# mspfacedraft.net
KiCad netlist of a schematic drawn in EAGLE
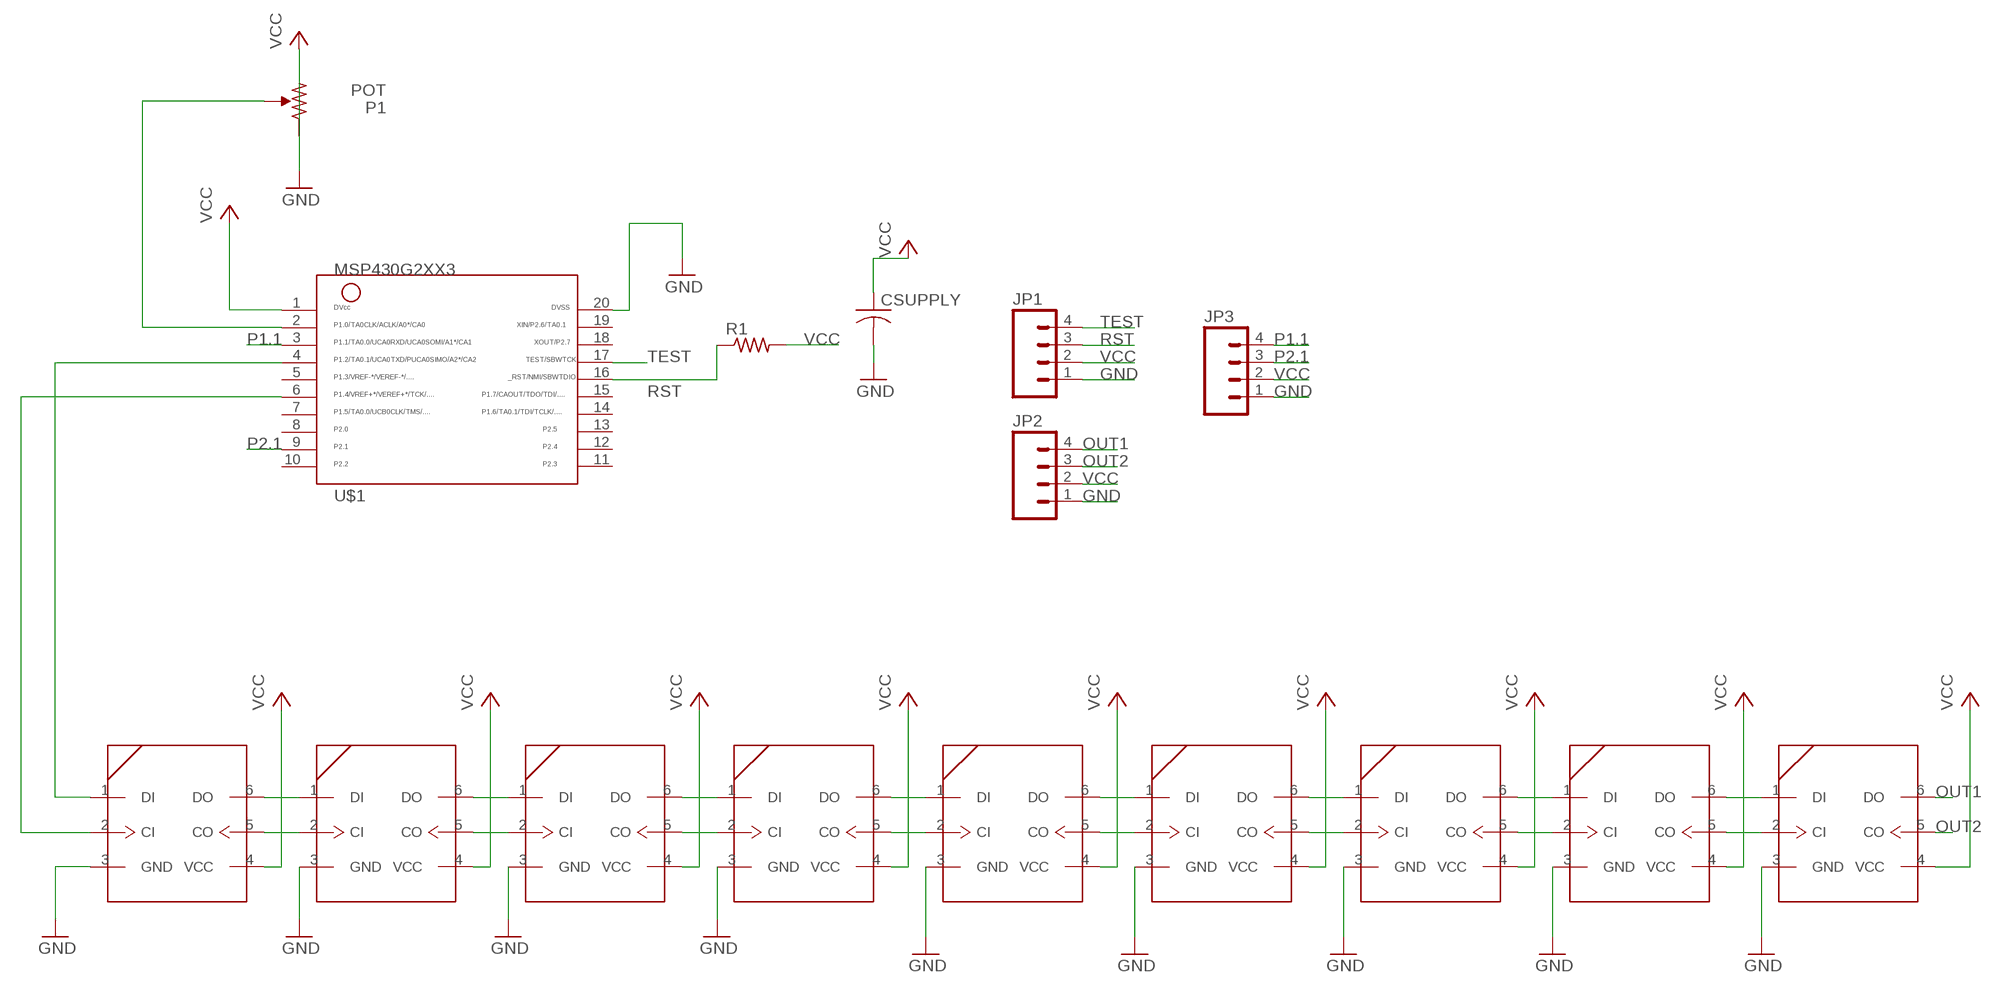
[diagram p0: schematic, sheet 1]

(export (version "E")
  (design (tool "Eeschema 10.0.6"))
  (components
    (comp (ref "CSUPPLY")
      (value "C-USC1206")
      (footprint "eagle-import:C1206")
      (libsource (lib "eagle-import") (part "C-USC1206"))
    )
    (comp (ref "JP1")
      (value "M04LOCK")
      (footprint "eagle-import:1X04_LOCK")
      (libsource (lib "eagle-import") (part "M04LOCK"))
    )
    (comp (ref "JP2")
      (value "M04LOCK")
      (footprint "eagle-import:1X04_LOCK")
      (libsource (lib "eagle-import") (part "M04LOCK"))
    )
    (comp (ref "JP3")
      (value "M04LOCK")
      (footprint "eagle-import:1X04_LOCK")
      (libsource (lib "eagle-import") (part "M04LOCK"))
    )
    (comp (ref "LED1")
      (value "APA102")
      (footprint "eagle-import:5050")
      (libsource (lib "eagle-import") (part "APA102"))
    )
    (comp (ref "LED2")
      (value "APA102")
      (footprint "eagle-import:5050")
      (libsource (lib "eagle-import") (part "APA102"))
    )
    (comp (ref "LED3")
      (value "APA102")
      (footprint "eagle-import:5050")
      (libsource (lib "eagle-import") (part "APA102"))
    )
    (comp (ref "LED4")
      (value "APA102")
      (footprint "eagle-import:5050")
      (libsource (lib "eagle-import") (part "APA102"))
    )
    (comp (ref "LED5")
      (value "APA102")
      (footprint "eagle-import:5050")
      (libsource (lib "eagle-import") (part "APA102"))
    )
    (comp (ref "LED6")
      (value "APA102")
      (footprint "eagle-import:5050")
      (libsource (lib "eagle-import") (part "APA102"))
    )
    (comp (ref "LED7")
      (value "APA102")
      (footprint "eagle-import:5050")
      (libsource (lib "eagle-import") (part "APA102"))
    )
    (comp (ref "LED8")
      (value "APA102")
      (footprint "eagle-import:5050")
      (libsource (lib "eagle-import") (part "APA102"))
    )
    (comp (ref "LED9")
      (value "APA102")
      (footprint "eagle-import:5050")
      (libsource (lib "eagle-import") (part "APA102"))
    )
    (comp (ref "P1")
      (value "POT")
      (footprint "eagle-import:POT")
      (libsource (lib "eagle-import") (part "POT"))
    )
    (comp (ref "R1")
      (value "R-US_R1206")
      (footprint "eagle-import:R1206")
      (libsource (lib "eagle-import") (part "R-US_R1206"))
    )
    (comp (ref "U$1")
      (value "MSP430G2XX3TSSOP")
      (footprint "eagle-import:PW20")
      (libsource (lib "eagle-import") (part "MSP430G2XX3TSSOP"))
    )
  )
  (nets
    (net (code "1") (name "/OUT1") (class "Default")
      (node (ref "JP2") (pin "4") (pinfunction "4_4") (pintype "passive"))
      (node (ref "LED9") (pin "6") (pinfunction "DO_6") (pintype "output"))
    )
    (net (code "2") (name "/OUT2") (class "Default")
      (node (ref "JP2") (pin "3") (pinfunction "3_3") (pintype "passive"))
      (node (ref "LED9") (pin "5") (pinfunction "CO_5") (pintype "output"))
    )
    (net (code "3") (name "/P1.1") (class "Default")
      (node (ref "JP3") (pin "4") (pinfunction "4_4") (pintype "passive"))
      (node (ref "U$1") (pin "3") (pinfunction "3_3") (pintype "bidirectional"))
    )
    (net (code "4") (name "/P2.1") (class "Default")
      (node (ref "JP3") (pin "3") (pinfunction "3_3") (pintype "passive"))
      (node (ref "U$1") (pin "9") (pinfunction "9_9") (pintype "bidirectional"))
    )
    (net (code "5") (name "/RST") (class "Default")
      (node (ref "JP1") (pin "3") (pinfunction "3_3") (pintype "passive"))
      (node (ref "R1") (pin "1") (pinfunction "1_1") (pintype "passive"))
      (node (ref "U$1") (pin "16") (pinfunction "16_16") (pintype "bidirectional"))
    )
    (net (code "6") (name "/TEST") (class "Default")
      (node (ref "JP1") (pin "4") (pinfunction "4_4") (pintype "passive"))
      (node (ref "U$1") (pin "17") (pinfunction "17_17") (pintype "bidirectional"))
    )
    (net (code "7") (name "GND") (class "Default")
      (node (ref "CSUPPLY") (pin "2") (pinfunction "2_2") (pintype "passive"))
      (node (ref "JP1") (pin "1") (pinfunction "1_1") (pintype "passive"))
      (node (ref "JP2") (pin "1") (pinfunction "1_1") (pintype "passive"))
      (node (ref "JP3") (pin "1") (pinfunction "1_1") (pintype "passive"))
      (node (ref "LED1") (pin "3") (pinfunction "GND_3") (pintype "power_in"))
      (node (ref "LED2") (pin "3") (pinfunction "GND_3") (pintype "power_in"))
      (node (ref "LED3") (pin "3") (pinfunction "GND_3") (pintype "power_in"))
      (node (ref "LED4") (pin "3") (pinfunction "GND_3") (pintype "power_in"))
      (node (ref "LED5") (pin "3") (pinfunction "GND_3") (pintype "power_in"))
      (node (ref "LED6") (pin "3") (pinfunction "GND_3") (pintype "power_in"))
      (node (ref "LED7") (pin "3") (pinfunction "GND_3") (pintype "power_in"))
      (node (ref "LED8") (pin "3") (pinfunction "GND_3") (pintype "power_in"))
      (node (ref "LED9") (pin "3") (pinfunction "GND_3") (pintype "power_in"))
      (node (ref "P1") (pin "GND") (pinfunction "CW_GND") (pintype "passive"))
      (node (ref "U$1") (pin "20") (pinfunction "20_20") (pintype "bidirectional"))
    )
    (net (code "8") (name "Net-(LED1-CI)") (class "Default")
      (node (ref "LED1") (pin "2") (pinfunction "CI_2") (pintype "input"))
      (node (ref "U$1") (pin "6") (pinfunction "6_6") (pintype "bidirectional"))
    )
    (net (code "9") (name "Net-(LED1-CO)") (class "Default")
      (node (ref "LED1") (pin "5") (pinfunction "CO_5") (pintype "output"))
      (node (ref "LED2") (pin "2") (pinfunction "CI_2") (pintype "input"))
    )
    (net (code "10") (name "Net-(LED1-DI)") (class "Default")
      (node (ref "LED1") (pin "1") (pinfunction "DI_1") (pintype "input"))
      (node (ref "U$1") (pin "4") (pinfunction "4_4") (pintype "bidirectional"))
    )
    (net (code "11") (name "Net-(LED1-DO)") (class "Default")
      (node (ref "LED1") (pin "6") (pinfunction "DO_6") (pintype "output"))
      (node (ref "LED2") (pin "1") (pinfunction "DI_1") (pintype "input"))
    )
    (net (code "12") (name "Net-(LED2-CO)") (class "Default")
      (node (ref "LED2") (pin "5") (pinfunction "CO_5") (pintype "output"))
      (node (ref "LED3") (pin "2") (pinfunction "CI_2") (pintype "input"))
    )
    (net (code "13") (name "Net-(LED2-DO)") (class "Default")
      (node (ref "LED2") (pin "6") (pinfunction "DO_6") (pintype "output"))
      (node (ref "LED3") (pin "1") (pinfunction "DI_1") (pintype "input"))
    )
    (net (code "14") (name "Net-(LED3-CO)") (class "Default")
      (node (ref "LED3") (pin "5") (pinfunction "CO_5") (pintype "output"))
      (node (ref "LED4") (pin "2") (pinfunction "CI_2") (pintype "input"))
    )
    (net (code "15") (name "Net-(LED3-DO)") (class "Default")
      (node (ref "LED3") (pin "6") (pinfunction "DO_6") (pintype "output"))
      (node (ref "LED4") (pin "1") (pinfunction "DI_1") (pintype "input"))
    )
    (net (code "16") (name "Net-(LED4-CO)") (class "Default")
      (node (ref "LED4") (pin "5") (pinfunction "CO_5") (pintype "output"))
      (node (ref "LED5") (pin "2") (pinfunction "CI_2") (pintype "input"))
    )
    (net (code "17") (name "Net-(LED4-DO)") (class "Default")
      (node (ref "LED4") (pin "6") (pinfunction "DO_6") (pintype "output"))
      (node (ref "LED5") (pin "1") (pinfunction "DI_1") (pintype "input"))
    )
    (net (code "18") (name "Net-(LED5-CO)") (class "Default")
      (node (ref "LED5") (pin "5") (pinfunction "CO_5") (pintype "output"))
      (node (ref "LED6") (pin "2") (pinfunction "CI_2") (pintype "input"))
    )
    (net (code "19") (name "Net-(LED5-DO)") (class "Default")
      (node (ref "LED5") (pin "6") (pinfunction "DO_6") (pintype "output"))
      (node (ref "LED6") (pin "1") (pinfunction "DI_1") (pintype "input"))
    )
    (net (code "20") (name "Net-(LED6-CO)") (class "Default")
      (node (ref "LED6") (pin "5") (pinfunction "CO_5") (pintype "output"))
      (node (ref "LED7") (pin "2") (pinfunction "CI_2") (pintype "input"))
    )
    (net (code "21") (name "Net-(LED6-DO)") (class "Default")
      (node (ref "LED6") (pin "6") (pinfunction "DO_6") (pintype "output"))
      (node (ref "LED7") (pin "1") (pinfunction "DI_1") (pintype "input"))
    )
    (net (code "22") (name "Net-(LED7-CO)") (class "Default")
      (node (ref "LED7") (pin "5") (pinfunction "CO_5") (pintype "output"))
      (node (ref "LED8") (pin "2") (pinfunction "CI_2") (pintype "input"))
    )
    (net (code "23") (name "Net-(LED7-DO)") (class "Default")
      (node (ref "LED7") (pin "6") (pinfunction "DO_6") (pintype "output"))
      (node (ref "LED8") (pin "1") (pinfunction "DI_1") (pintype "input"))
    )
    (net (code "24") (name "Net-(LED8-CO)") (class "Default")
      (node (ref "LED8") (pin "5") (pinfunction "CO_5") (pintype "output"))
      (node (ref "LED9") (pin "2") (pinfunction "CI_2") (pintype "input"))
    )
    (net (code "25") (name "Net-(LED8-DO)") (class "Default")
      (node (ref "LED8") (pin "6") (pinfunction "DO_6") (pintype "output"))
      (node (ref "LED9") (pin "1") (pinfunction "DI_1") (pintype "input"))
    )
    (net (code "26") (name "Net-(P1-S)") (class "Default")
      (node (ref "P1") (pin "SIG") (pinfunction "S_SIG") (pintype "bidirectional"))
      (node (ref "U$1") (pin "2") (pinfunction "2_2") (pintype "bidirectional"))
    )
    (net (code "27") (name "VCC") (class "Default")
      (node (ref "CSUPPLY") (pin "1") (pinfunction "1_1") (pintype "passive"))
      (node (ref "JP1") (pin "2") (pinfunction "2_2") (pintype "passive"))
      (node (ref "JP2") (pin "2") (pinfunction "2_2") (pintype "passive"))
      (node (ref "JP3") (pin "2") (pinfunction "2_2") (pintype "passive"))
      (node (ref "LED1") (pin "4") (pinfunction "VCC_4") (pintype "power_in"))
      (node (ref "LED2") (pin "4") (pinfunction "VCC_4") (pintype "power_in"))
      (node (ref "LED3") (pin "4") (pinfunction "VCC_4") (pintype "power_in"))
      (node (ref "LED4") (pin "4") (pinfunction "VCC_4") (pintype "power_in"))
      (node (ref "LED5") (pin "4") (pinfunction "VCC_4") (pintype "power_in"))
      (node (ref "LED6") (pin "4") (pinfunction "VCC_4") (pintype "power_in"))
      (node (ref "LED7") (pin "4") (pinfunction "VCC_4") (pintype "power_in"))
      (node (ref "LED8") (pin "4") (pinfunction "VCC_4") (pintype "power_in"))
      (node (ref "LED9") (pin "4") (pinfunction "VCC_4") (pintype "power_in"))
      (node (ref "P1") (pin "VDD") (pinfunction "CCW_VDD") (pintype "passive"))
      (node (ref "R1") (pin "2") (pinfunction "2_2") (pintype "passive"))
      (node (ref "U$1") (pin "1") (pinfunction "1_1") (pintype "bidirectional"))
    )
    (net (code "28") (name "unconnected-(U$1-Pad5)") (class "Default")
      (node (ref "U$1") (pin "5") (pinfunction "5_5") (pintype "bidirectional"))
    )
    (net (code "29") (name "unconnected-(U$1-Pad7)") (class "Default")
      (node (ref "U$1") (pin "7") (pinfunction "7_7") (pintype "bidirectional"))
    )
    (net (code "30") (name "unconnected-(U$1-Pad8)") (class "Default")
      (node (ref "U$1") (pin "8") (pinfunction "8_8") (pintype "bidirectional"))
    )
    (net (code "31") (name "unconnected-(U$1-Pad10)") (class "Default")
      (node (ref "U$1") (pin "10") (pinfunction "10_10") (pintype "bidirectional"))
    )
    (net (code "32") (name "unconnected-(U$1-Pad11)") (class "Default")
      (node (ref "U$1") (pin "11") (pinfunction "11_11") (pintype "bidirectional"))
    )
    (net (code "33") (name "unconnected-(U$1-Pad12)") (class "Default")
      (node (ref "U$1") (pin "12") (pinfunction "12_12") (pintype "bidirectional"))
    )
    (net (code "34") (name "unconnected-(U$1-Pad13)") (class "Default")
      (node (ref "U$1") (pin "13") (pinfunction "13_13") (pintype "bidirectional"))
    )
    (net (code "35") (name "unconnected-(U$1-Pad14)") (class "Default")
      (node (ref "U$1") (pin "14") (pinfunction "14_14") (pintype "bidirectional"))
    )
    (net (code "36") (name "unconnected-(U$1-Pad15)") (class "Default")
      (node (ref "U$1") (pin "15") (pinfunction "15_15") (pintype "bidirectional"))
    )
    (net (code "37") (name "unconnected-(U$1-Pad18)") (class "Default")
      (node (ref "U$1") (pin "18") (pinfunction "18_18") (pintype "bidirectional"))
    )
    (net (code "38") (name "unconnected-(U$1-Pad19)") (class "Default")
      (node (ref "U$1") (pin "19") (pinfunction "19_19") (pintype "bidirectional"))
    )
  )
)
